# v3.net
KiCad netlist of a schematic drawn in EAGLE
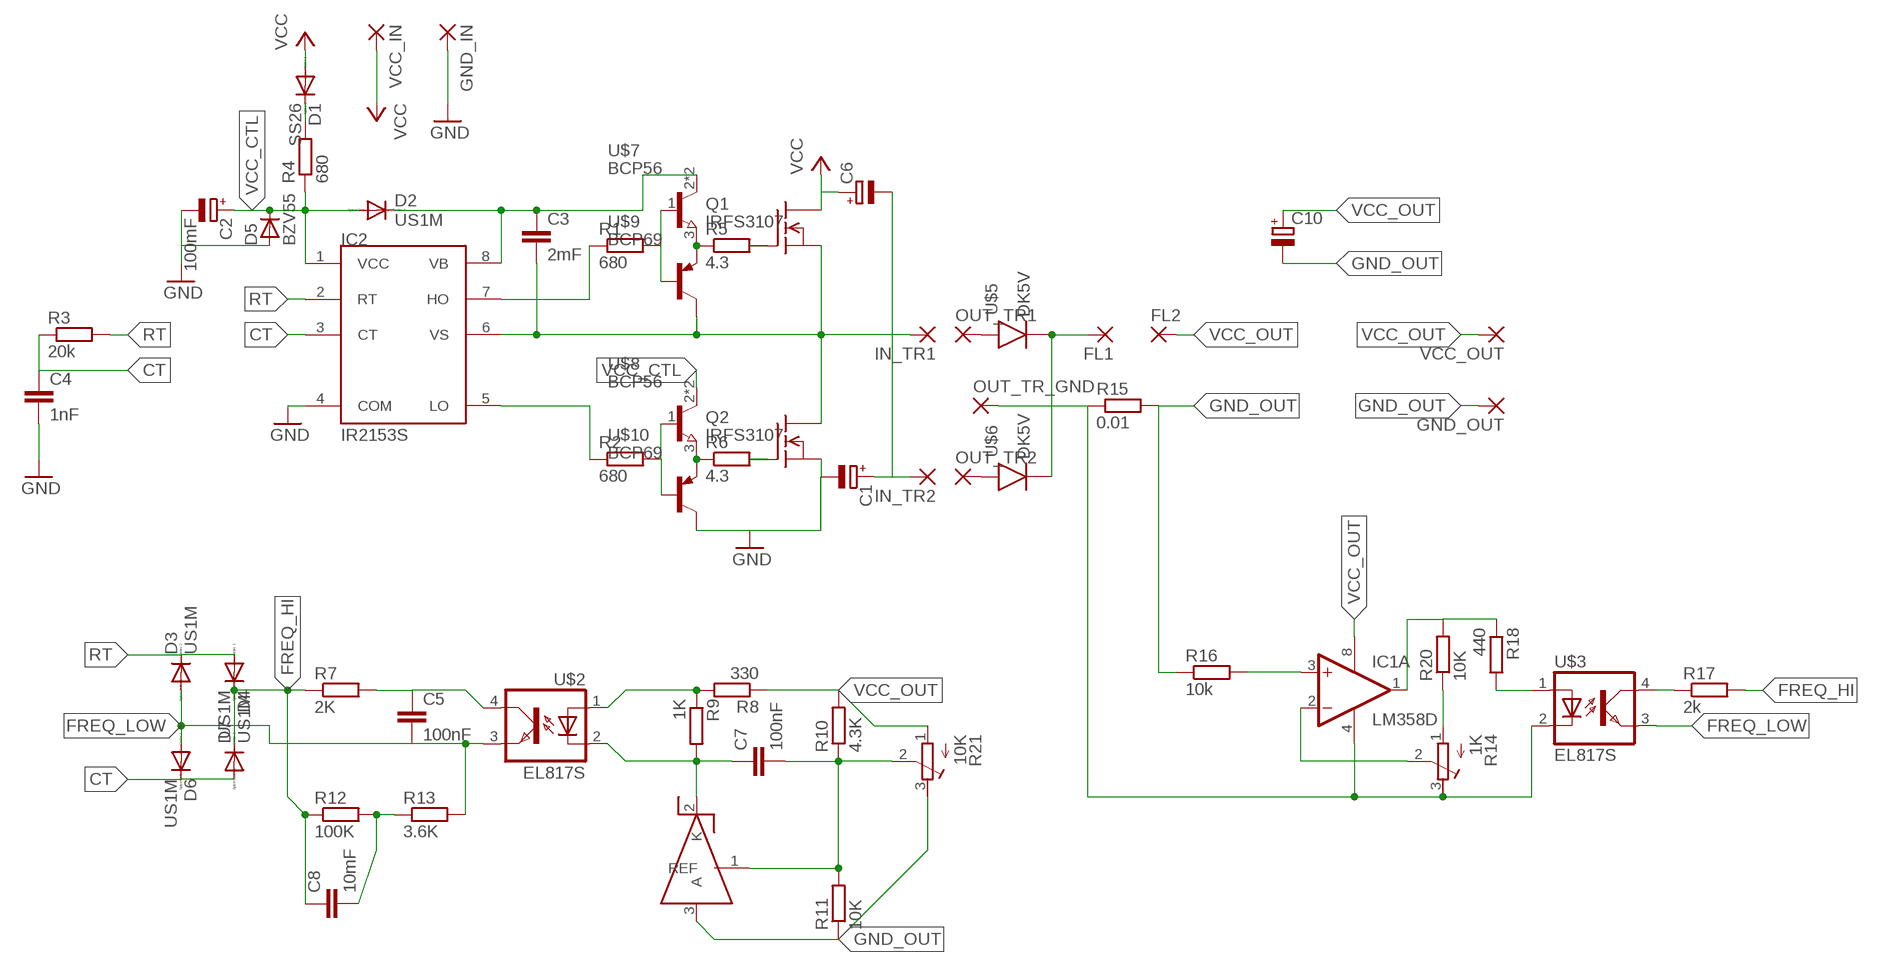
[diagram p0: schematic, sheet 1]

(export (version "E")
  (design (tool "Eeschema 10.0.6"))
  (components
    (comp (ref "C1")
      (value "CPOL-EUE10-22.5")
      (footprint "eagle-import:EB22,5D")
      (libsource (lib "eagle-import") (part "CPOL-EUE10-22.5"))
    )
    (comp (ref "C2")
      (value "100mF")
      (footprint "eagle-import:E5-10,5")
      (libsource (lib "eagle-import") (part "CPOL-EUE5-10.5"))
    )
    (comp (ref "C3")
      (value "2mF")
      (footprint "eagle-import:C0805")
      (libsource (lib "eagle-import") (part "C-EUC0805"))
    )
    (comp (ref "C4")
      (value "1nF")
      (footprint "eagle-import:C0805")
      (libsource (lib "eagle-import") (part "C-EUC0805"))
    )
    (comp (ref "C5")
      (value "100nF")
      (footprint "eagle-import:C0805")
      (libsource (lib "eagle-import") (part "C-EUC0805"))
    )
    (comp (ref "C6")
      (value "CPOL-EUE10-22.5")
      (footprint "eagle-import:EB22,5D")
      (libsource (lib "eagle-import") (part "CPOL-EUE10-22.5"))
    )
    (comp (ref "C7")
      (value "100nF")
      (footprint "eagle-import:C0805")
      (libsource (lib "eagle-import") (part "resistor_C-EUC0805"))
    )
    (comp (ref "C8")
      (value "10mF")
      (footprint "eagle-import:C0805")
      (libsource (lib "eagle-import") (part "C-EUC0805"))
    )
    (comp (ref "C10")
      (value "CPOL-EUE7.5-18")
      (footprint "eagle-import:E7,5-18")
      (libsource (lib "eagle-import") (part "CPOL-EUE7.5-18"))
    )
    (comp (ref "D1")
      (value "SS26")
      (footprint "eagle-import:DO-214AC")
      (libsource (lib "eagle-import") (part "DIODE-DO-214AC"))
    )
    (comp (ref "D2")
      (value "US1M")
      (footprint "eagle-import:DO-214AC")
      (libsource (lib "eagle-import") (part "DIODE-DO-214AC"))
    )
    (comp (ref "D3")
      (value "US1M")
      (footprint "eagle-import:DO-214AC")
      (libsource (lib "eagle-import") (part "DIODE-DO-214AC"))
    )
    (comp (ref "D4")
      (value "US1M")
      (footprint "eagle-import:DO-214AC")
      (libsource (lib "eagle-import") (part "DIODE-DO-214AC"))
    )
    (comp (ref "D5")
      (value "BZV55")
      (footprint "eagle-import:SOD80")
      (libsource (lib "eagle-import") (part "D-SOD-80"))
    )
    (comp (ref "D6")
      (value "US1M")
      (footprint "eagle-import:DO-214AC")
      (libsource (lib "eagle-import") (part "DIODE-DO-214AC"))
    )
    (comp (ref "D7")
      (value "US1M")
      (footprint "eagle-import:DO-214AC")
      (libsource (lib "eagle-import") (part "DIODE-DO-214AC"))
    )
    (comp (ref "FL1")
      (value "3,81/1,4")
      (footprint "eagle-import:3,81_1,4")
      (libsource (lib "eagle-import") (part "3,81/1,4"))
    )
    (comp (ref "FL2")
      (value "3,81/1,4")
      (footprint "eagle-import:3,81_1,4")
      (libsource (lib "eagle-import") (part "3,81/1,4"))
    )
    (comp (ref "GND_IN")
      (value "3,81/1,4")
      (footprint "eagle-import:3,81_1,4")
      (libsource (lib "eagle-import") (part "3,81/1,4"))
    )
    (comp (ref "GND_OUT")
      (value "3,81/1,4")
      (footprint "eagle-import:3,81_1,4")
      (libsource (lib "eagle-import") (part "3,81/1,4"))
    )
    (comp (ref "IC1")
      (value "LM358D")
      (footprint "eagle-import:SO08")
      (libsource (lib "eagle-import") (part "LM358D"))
    )
    (comp (ref "IC2")
      (value "IR2153S")
      (footprint "eagle-import:SO08")
      (libsource (lib "eagle-import") (part "IR2153S"))
    )
    (comp (ref "IN_TR1")
      (value "3,81/1,4")
      (footprint "eagle-import:3,81_1,4")
      (libsource (lib "eagle-import") (part "3,81/1,4"))
    )
    (comp (ref "IN_TR2")
      (value "3,81/1,4")
      (footprint "eagle-import:3,81_1,4")
      (libsource (lib "eagle-import") (part "3,81/1,4"))
    )
    (comp (ref "OUT_TR1")
      (value "3,81/1,4")
      (footprint "eagle-import:3,81_1,4")
      (libsource (lib "eagle-import") (part "3,81/1,4"))
    )
    (comp (ref "OUT_TR2")
      (value "3,81/1,4")
      (footprint "eagle-import:3,81_1,4")
      (libsource (lib "eagle-import") (part "3,81/1,4"))
    )
    (comp (ref "OUT_TR_GND")
      (value "3,81/1,4")
      (footprint "eagle-import:3,81_1,4")
      (libsource (lib "eagle-import") (part "3,81/1,4"))
    )
    (comp (ref "Q1")
      (value "IRFS3107")
      (footprint "eagle-import:D2PAK")
      (libsource (lib "eagle-import") (part "IRF510D2PAK"))
    )
    (comp (ref "Q2")
      (value "IRFS3107")
      (footprint "eagle-import:D2PAK")
      (libsource (lib "eagle-import") (part "IRF510D2PAK"))
    )
    (comp (ref "R1")
      (value "680")
      (footprint "eagle-import:R0805")
      (libsource (lib "eagle-import") (part "R-EU_R0805"))
    )
    (comp (ref "R2")
      (value "680")
      (footprint "eagle-import:R0805")
      (libsource (lib "eagle-import") (part "R-EU_R0805"))
    )
    (comp (ref "R3")
      (value "20k")
      (footprint "eagle-import:R0805")
      (libsource (lib "eagle-import") (part "R-EU_R0805"))
    )
    (comp (ref "R4")
      (value "680")
      (footprint "eagle-import:R0805")
      (libsource (lib "eagle-import") (part "R-EU_R0805"))
    )
    (comp (ref "R5")
      (value "4.3")
      (footprint "eagle-import:R0805")
      (libsource (lib "eagle-import") (part "R-EU_R0805"))
    )
    (comp (ref "R6")
      (value "4.3")
      (footprint "eagle-import:R0805")
      (libsource (lib "eagle-import") (part "R-EU_R0805"))
    )
    (comp (ref "R7")
      (value "2K")
      (footprint "eagle-import:R0805")
      (libsource (lib "eagle-import") (part "R-EU_R0805"))
    )
    (comp (ref "R8")
      (value "330")
      (footprint "eagle-import:R0805")
      (libsource (lib "eagle-import") (part "resistor_R-EU_R0805"))
    )
    (comp (ref "R9")
      (value "1K")
      (footprint "eagle-import:R0805")
      (libsource (lib "eagle-import") (part "resistor_R-EU_R0805"))
    )
    (comp (ref "R10")
      (value "4.3K")
      (footprint "eagle-import:R0805")
      (libsource (lib "eagle-import") (part "resistor_R-EU_R0805"))
    )
    (comp (ref "R11")
      (value "10K")
      (footprint "eagle-import:R0805")
      (libsource (lib "eagle-import") (part "resistor_R-EU_R0805"))
    )
    (comp (ref "R12")
      (value "100K")
      (footprint "eagle-import:R0805")
      (libsource (lib "eagle-import") (part "R-EU_R0805"))
    )
    (comp (ref "R13")
      (value "3.6K")
      (footprint "eagle-import:R0805")
      (libsource (lib "eagle-import") (part "R-EU_R0805"))
    )
    (comp (ref "R14")
      (value "1K")
      (footprint "eagle-import:RTRIM3296W")
      (libsource (lib "eagle-import") (part "R-TRIMM3296W"))
    )
    (comp (ref "R15")
      (value "0.01")
      (footprint "eagle-import:R2512")
      (libsource (lib "eagle-import") (part "R-EU_R2512"))
    )
    (comp (ref "R16")
      (value "10k")
      (footprint "eagle-import:M0805")
      (libsource (lib "eagle-import") (part "R-EU_M0805"))
    )
    (comp (ref "R17")
      (value "2k")
      (footprint "eagle-import:M0805")
      (libsource (lib "eagle-import") (part "R-EU_M0805"))
    )
    (comp (ref "R18")
      (value "440")
      (footprint "eagle-import:M0805")
      (libsource (lib "eagle-import") (part "R-EU_M0805"))
    )
    (comp (ref "R20")
      (value "10K")
      (footprint "eagle-import:M0805")
      (libsource (lib "eagle-import") (part "R-EU_M0805"))
    )
    (comp (ref "R21")
      (value "10K")
      (footprint "eagle-import:RTRIM3296W")
      (libsource (lib "eagle-import") (part "R-TRIMM3296W"))
    )
    (comp (ref "U$1")
      (value "TL431")
      (footprint "eagle-import:SOT23")
      (libsource (lib "eagle-import") (part "TL431AIDBZR"))
    )
    (comp (ref "U$2")
      (value "EL817S")
      (footprint "eagle-import:SMD4_L")
      (libsource (lib "eagle-import") (part "EL817S"))
    )
    (comp (ref "U$3")
      (value "EL817S")
      (footprint "eagle-import:SMD4_L")
      (libsource (lib "eagle-import") (part "EL817S"))
    )
    (comp (ref "U$5")
      (value "DK5V")
      (footprint "eagle-import:TO220(V)")
      (libsource (lib "eagle-import") (part "DK5V100R10ST1"))
    )
    (comp (ref "U$6")
      (value "DK5V")
      (footprint "eagle-import:TO220(V)")
      (libsource (lib "eagle-import") (part "DK5V100R10ST1"))
    )
    (comp (ref "U$7")
      (value "BCP56")
      (footprint "eagle-import:SOT223")
      (libsource (lib "eagle-import") (part "BCP56"))
    )
    (comp (ref "U$8")
      (value "BCP56")
      (footprint "eagle-import:SOT223")
      (libsource (lib "eagle-import") (part "BCP56"))
    )
    (comp (ref "U$9")
      (value "BCP69")
      (footprint "eagle-import:SOT223")
      (libsource (lib "eagle-import") (part "BCP69"))
    )
    (comp (ref "U$10")
      (value "BCP69")
      (footprint "eagle-import:SOT223")
      (libsource (lib "eagle-import") (part "BCP69"))
    )
    (comp (ref "VCC_IN")
      (value "3,81/1,4")
      (footprint "eagle-import:3,81_1,4")
      (libsource (lib "eagle-import") (part "3,81/1,4"))
    )
    (comp (ref "VCC_OUT")
      (value "3,81/1,4")
      (footprint "eagle-import:3,81_1,4")
      (libsource (lib "eagle-import") (part "3,81/1,4"))
    )
  )
  (nets
    (net (code "1") (name "CT") (class "Default")
      (node (ref "C4") (pin "1") (pinfunction "1_1") (pintype "passive"))
      (node (ref "D6") (pin "C") (pinfunction "C_C") (pintype "passive"))
      (node (ref "D7") (pin "A") (pinfunction "A_A") (pintype "passive"))
      (node (ref "IC2") (pin "3") (pinfunction "CT_3") (pintype "input"))
      (node (ref "R3") (pin "1") (pinfunction "1_1") (pintype "passive"))
    )
    (net (code "2") (name "FREQ_HI") (class "Default")
      (node (ref "C8") (pin "1") (pinfunction "1_1") (pintype "passive"))
      (node (ref "D4") (pin "C") (pinfunction "C_C") (pintype "passive"))
      (node (ref "D7") (pin "C") (pinfunction "C_C") (pintype "passive"))
      (node (ref "R12") (pin "1") (pinfunction "1_1") (pintype "passive"))
      (node (ref "R17") (pin "2") (pinfunction "2_2") (pintype "passive"))
      (node (ref "R7") (pin "1") (pinfunction "1_1") (pintype "passive"))
    )
    (net (code "3") (name "FREQ_LOW") (class "Default")
      (node (ref "C5") (pin "2") (pinfunction "2_2") (pintype "passive"))
      (node (ref "D3") (pin "A") (pinfunction "A_A") (pintype "passive"))
      (node (ref "D6") (pin "A") (pinfunction "A_A") (pintype "passive"))
      (node (ref "R13") (pin "2") (pinfunction "2_2") (pintype "passive"))
      (node (ref "U$2") (pin "3") (pinfunction "EMIT_3") (pintype "passive"))
      (node (ref "U$3") (pin "3") (pinfunction "EMIT_3") (pintype "passive"))
    )
    (net (code "4") (name "GND") (class "Default")
      (node (ref "C1") (pin "-") (pinfunction "-_-") (pintype "passive"))
      (node (ref "C2") (pin "-") (pinfunction "-_-") (pintype "passive"))
      (node (ref "C4") (pin "2") (pinfunction "2_2") (pintype "passive"))
      (node (ref "D5") (pin "2") (pinfunction "A_2") (pintype "passive"))
      (node (ref "GND_IN") (pin "1") (pinfunction "P_1") (pintype "passive"))
      (node (ref "IC2") (pin "4") (pinfunction "COM_4") (pintype "power_in"))
      (node (ref "Q2") (pin "3") (pinfunction "S_3") (pintype "passive"))
      (node (ref "U$10") (pin "2") (pinfunction "C_2") (pintype "passive"))
      (node (ref "U$10") (pin "4") (pinfunction "C_4") (pintype "passive"))
    )
    (net (code "5") (name "GND_OUT") (class "Default")
      (node (ref "C10") (pin "-") (pinfunction "-_-") (pintype "passive"))
      (node (ref "GND_OUT") (pin "1") (pinfunction "P_1") (pintype "passive"))
      (node (ref "R11") (pin "1") (pinfunction "1_1") (pintype "passive"))
      (node (ref "R15") (pin "2") (pinfunction "2_2") (pintype "passive"))
      (node (ref "R16") (pin "1") (pinfunction "1_1") (pintype "passive"))
      (node (ref "R21") (pin "3") (pinfunction "E_3") (pintype "passive"))
      (node (ref "U$1") (pin "3") (pinfunction "A_3") (pintype "bidirectional"))
    )
    (net (code "6") (name "Net-(C8-Pad2)") (class "Default")
      (node (ref "C8") (pin "2") (pinfunction "2_2") (pintype "passive"))
      (node (ref "R12") (pin "2") (pinfunction "2_2") (pintype "passive"))
      (node (ref "R13") (pin "1") (pinfunction "1_1") (pintype "passive"))
    )
    (net (code "7") (name "Net-(D1-PadC)") (class "Default")
      (node (ref "D1") (pin "C") (pinfunction "C_C") (pintype "passive"))
      (node (ref "R4") (pin "2") (pinfunction "2_2") (pintype "passive"))
    )
    (net (code "8") (name "Net-(FL1-P)") (class "Default")
      (node (ref "FL1") (pin "1") (pinfunction "P_1") (pintype "passive"))
      (node (ref "U$5") (pin "GND") (pinfunction "K_GND") (pintype "passive"))
      (node (ref "U$6") (pin "GND") (pinfunction "K_GND") (pintype "passive"))
    )
    (net (code "9") (name "Net-(IC1A-+IN)") (class "Default")
      (node (ref "IC1") (pin "3") (pinfunction "+IN_3") (pintype "input"))
      (node (ref "R16") (pin "2") (pinfunction "2_2") (pintype "passive"))
    )
    (net (code "10") (name "Net-(IC1A--IN)") (class "Default")
      (node (ref "IC1") (pin "2") (pinfunction "-IN_2") (pintype "input"))
      (node (ref "R14") (pin "2") (pinfunction "S_2") (pintype "passive"))
    )
    (net (code "11") (name "Net-(IC1A-OUT)") (class "Default")
      (node (ref "IC1") (pin "1") (pinfunction "OUT_1") (pintype "output"))
      (node (ref "R18") (pin "1") (pinfunction "1_1") (pintype "passive"))
      (node (ref "R20") (pin "2") (pinfunction "2_2") (pintype "passive"))
    )
    (net (code "12") (name "Net-(IC1C-V-)") (class "Default")
      (node (ref "IC1") (pin "4") (pinfunction "V-_4") (pintype "power_in"))
      (node (ref "OUT_TR_GND") (pin "1") (pinfunction "P_1") (pintype "passive"))
      (node (ref "R14") (pin "3") (pinfunction "E_3") (pintype "passive"))
      (node (ref "R15") (pin "1") (pinfunction "1_1") (pintype "passive"))
      (node (ref "U$3") (pin "2") (pinfunction "C_2") (pintype "passive"))
    )
    (net (code "13") (name "Net-(IC2-HO)") (class "Default")
      (node (ref "IC2") (pin "7") (pinfunction "HO_7") (pintype "output"))
      (node (ref "R1") (pin "1") (pinfunction "1_1") (pintype "passive"))
    )
    (net (code "14") (name "Net-(IC2-LO)") (class "Default")
      (node (ref "IC2") (pin "5") (pinfunction "LO_5") (pintype "output"))
      (node (ref "R2") (pin "1") (pinfunction "1_1") (pintype "passive"))
    )
    (net (code "15") (name "Net-(IC2-VB)") (class "Default")
      (node (ref "C3") (pin "1") (pinfunction "1_1") (pintype "passive"))
      (node (ref "D2") (pin "C") (pinfunction "C_C") (pintype "passive"))
      (node (ref "IC2") (pin "8") (pinfunction "VB_8") (pintype "power_in"))
      (node (ref "U$7") (pin "2") (pinfunction "C_2") (pintype "passive"))
      (node (ref "U$7") (pin "4") (pinfunction "C_4") (pintype "passive"))
    )
    (net (code "16") (name "Net-(IC2-VS)") (class "Default")
      (node (ref "C3") (pin "2") (pinfunction "2_2") (pintype "passive"))
      (node (ref "IC2") (pin "6") (pinfunction "VS_6") (pintype "power_in"))
      (node (ref "IN_TR1") (pin "1") (pinfunction "P_1") (pintype "passive"))
      (node (ref "Q1") (pin "3") (pinfunction "S_3") (pintype "passive"))
      (node (ref "Q2") (pin "2") (pinfunction "D_2") (pintype "passive"))
      (node (ref "U$9") (pin "2") (pinfunction "C_2") (pintype "passive"))
      (node (ref "U$9") (pin "4") (pinfunction "C_4") (pintype "passive"))
    )
    (net (code "17") (name "Net-(IN_TR2-P)") (class "Default")
      (node (ref "C1") (pin "+") (pinfunction "+_+") (pintype "passive"))
      (node (ref "C6") (pin "-") (pinfunction "-_-") (pintype "passive"))
      (node (ref "IN_TR2") (pin "1") (pinfunction "P_1") (pintype "passive"))
    )
    (net (code "18") (name "Net-(OUT_TR1-P)") (class "Default")
      (node (ref "OUT_TR1") (pin "1") (pinfunction "P_1") (pintype "passive"))
      (node (ref "U$5") (pin "IN") (pinfunction "A_IN") (pintype "passive"))
    )
    (net (code "19") (name "Net-(OUT_TR2-P)") (class "Default")
      (node (ref "OUT_TR2") (pin "1") (pinfunction "P_1") (pintype "passive"))
      (node (ref "U$6") (pin "IN") (pinfunction "A_IN") (pintype "passive"))
    )
    (net (code "20") (name "Net-(Q1-G)") (class "Default")
      (node (ref "Q1") (pin "1") (pinfunction "G_1") (pintype "passive"))
      (node (ref "R5") (pin "2") (pinfunction "2_2") (pintype "passive"))
    )
    (net (code "21") (name "Net-(Q2-G)") (class "Default")
      (node (ref "Q2") (pin "1") (pinfunction "G_1") (pintype "passive"))
      (node (ref "R6") (pin "2") (pinfunction "2_2") (pintype "passive"))
    )
    (net (code "22") (name "Net-(R14-A)") (class "Default")
      (node (ref "R14") (pin "1") (pinfunction "A_1") (pintype "passive"))
      (node (ref "R20") (pin "1") (pinfunction "1_1") (pintype "passive"))
    )
    (net (code "23") (name "Net-(R21-S)") (class "Default")
      (node (ref "C7") (pin "2") (pinfunction "2_2") (pintype "passive"))
      (node (ref "R10") (pin "1") (pinfunction "1_1") (pintype "passive"))
      (node (ref "R11") (pin "2") (pinfunction "2_2") (pintype "passive"))
      (node (ref "R21") (pin "2") (pinfunction "S_2") (pintype "passive"))
      (node (ref "U$1") (pin "1") (pinfunction "REF_1") (pintype "bidirectional"))
    )
    (net (code "24") (name "Net-(U$1-K)") (class "Default")
      (node (ref "C7") (pin "1") (pinfunction "1_1") (pintype "passive"))
      (node (ref "R9") (pin "2") (pinfunction "2_2") (pintype "passive"))
      (node (ref "U$1") (pin "2") (pinfunction "K_2") (pintype "bidirectional"))
      (node (ref "U$2") (pin "2") (pinfunction "C_2") (pintype "passive"))
    )
    (net (code "25") (name "Net-(U$2-A)") (class "Default")
      (node (ref "R8") (pin "2") (pinfunction "2_2") (pintype "passive"))
      (node (ref "R9") (pin "1") (pinfunction "1_1") (pintype "passive"))
      (node (ref "U$2") (pin "1") (pinfunction "A_1") (pintype "passive"))
    )
    (net (code "26") (name "Net-(U$2-COL)") (class "Default")
      (node (ref "C5") (pin "1") (pinfunction "1_1") (pintype "passive"))
      (node (ref "R7") (pin "2") (pinfunction "2_2") (pintype "passive"))
      (node (ref "U$2") (pin "4") (pinfunction "COL_4") (pintype "passive"))
    )
    (net (code "27") (name "Net-(U$3-A)") (class "Default")
      (node (ref "R18") (pin "2") (pinfunction "2_2") (pintype "passive"))
      (node (ref "U$3") (pin "1") (pinfunction "A_1") (pintype "passive"))
    )
    (net (code "28") (name "Net-(U$3-COL)") (class "Default")
      (node (ref "R17") (pin "1") (pinfunction "1_1") (pintype "passive"))
      (node (ref "U$3") (pin "4") (pinfunction "COL_4") (pintype "passive"))
    )
    (net (code "29") (name "Net-(U$7-B)") (class "Default")
      (node (ref "R1") (pin "2") (pinfunction "2_2") (pintype "passive"))
      (node (ref "U$7") (pin "1") (pinfunction "B_1") (pintype "passive"))
      (node (ref "U$9") (pin "1") (pinfunction "B_1") (pintype "passive"))
    )
    (net (code "30") (name "Net-(U$7-E)") (class "Default")
      (node (ref "R5") (pin "1") (pinfunction "1_1") (pintype "passive"))
      (node (ref "U$7") (pin "3") (pinfunction "E_3") (pintype "passive"))
      (node (ref "U$9") (pin "3") (pinfunction "E_3") (pintype "passive"))
    )
    (net (code "31") (name "Net-(U$10-B)") (class "Default")
      (node (ref "R2") (pin "2") (pinfunction "2_2") (pintype "passive"))
      (node (ref "U$10") (pin "1") (pinfunction "B_1") (pintype "passive"))
      (node (ref "U$8") (pin "1") (pinfunction "B_1") (pintype "passive"))
    )
    (net (code "32") (name "Net-(U$10-E)") (class "Default")
      (node (ref "R6") (pin "1") (pinfunction "1_1") (pintype "passive"))
      (node (ref "U$10") (pin "3") (pinfunction "E_3") (pintype "passive"))
      (node (ref "U$8") (pin "3") (pinfunction "E_3") (pintype "passive"))
    )
    (net (code "33") (name "RT") (class "Default")
      (node (ref "D3") (pin "C") (pinfunction "C_C") (pintype "passive"))
      (node (ref "D4") (pin "A") (pinfunction "A_A") (pintype "passive"))
      (node (ref "IC2") (pin "2") (pinfunction "RT_2") (pintype "output"))
      (node (ref "R3") (pin "2") (pinfunction "2_2") (pintype "passive"))
    )
    (net (code "34") (name "VCC") (class "Default")
      (node (ref "C6") (pin "+") (pinfunction "+_+") (pintype "passive"))
      (node (ref "D1") (pin "A") (pinfunction "A_A") (pintype "passive"))
      (node (ref "Q1") (pin "2") (pinfunction "D_2") (pintype "passive"))
      (node (ref "VCC_IN") (pin "1") (pinfunction "P_1") (pintype "passive"))
    )
    (net (code "35") (name "VCC_CTL") (class "Default")
      (node (ref "C2") (pin "+") (pinfunction "+_+") (pintype "passive"))
      (node (ref "D2") (pin "A") (pinfunction "A_A") (pintype "passive"))
      (node (ref "D5") (pin "1") (pinfunction "C_1") (pintype "passive"))
      (node (ref "IC2") (pin "1") (pinfunction "VCC_1") (pintype "power_in"))
      (node (ref "R4") (pin "1") (pinfunction "1_1") (pintype "passive"))
      (node (ref "U$8") (pin "2") (pinfunction "C_2") (pintype "passive"))
      (node (ref "U$8") (pin "4") (pinfunction "C_4") (pintype "passive"))
    )
    (net (code "36") (name "VCC_OUT") (class "Default")
      (node (ref "C10") (pin "+") (pinfunction "+_+") (pintype "passive"))
      (node (ref "FL2") (pin "1") (pinfunction "P_1") (pintype "passive"))
      (node (ref "IC1") (pin "8") (pinfunction "V+_8") (pintype "power_in"))
      (node (ref "R10") (pin "2") (pinfunction "2_2") (pintype "passive"))
      (node (ref "R21") (pin "1") (pinfunction "A_1") (pintype "passive"))
      (node (ref "R8") (pin "1") (pinfunction "1_1") (pintype "passive"))
      (node (ref "VCC_OUT") (pin "1") (pinfunction "P_1") (pintype "passive"))
    )
  )
)
